# H01R0_Frontend_1.net
KiCad netlist of a schematic drawn in Altium Designer
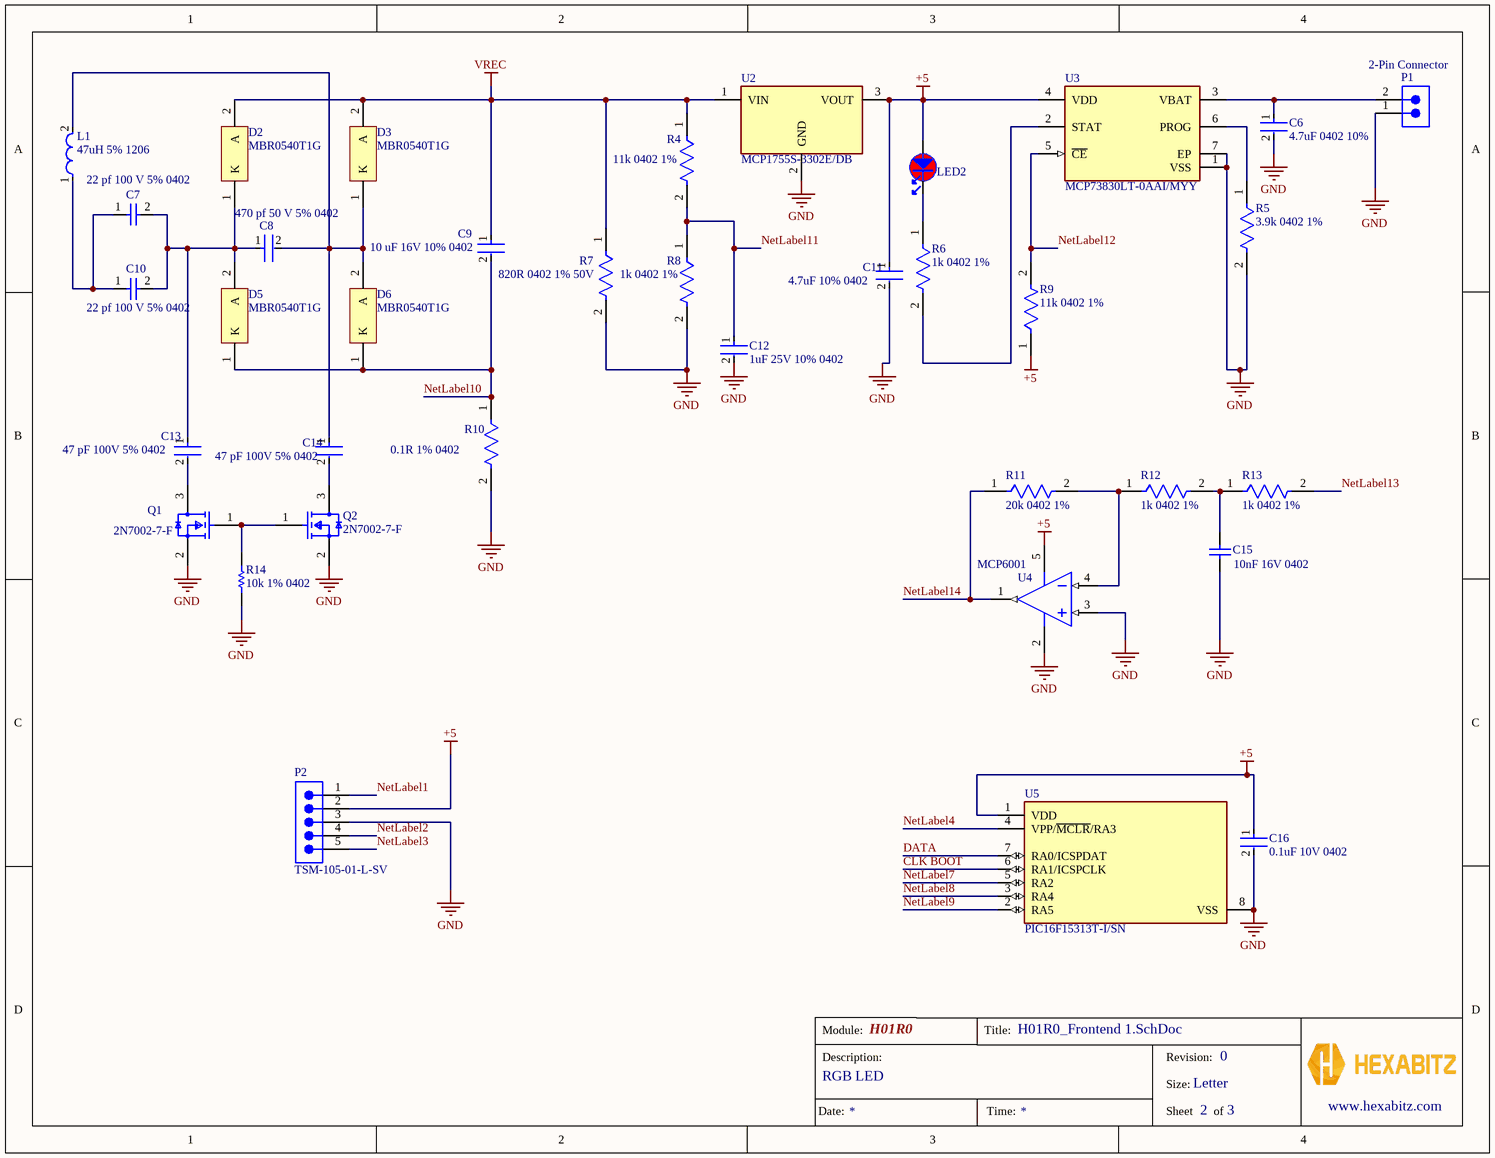
[diagram p0: H01R0_Frontend 1.SchDoc]

(export (version "E")
  (design (tool "Eeschema 10.0.6"))
  (components
    (comp (ref "C6")
      (value "4.7uF 0402 10%")
      (footprint "FP-GRM188-0_2-IPC_A")
      (description "Chip Multilayer Ceramic Capacitors for General Purpose, 0603, 4.7uF, X7S, 22%, 10%, 16V")
      (fields (field (name "TOLERANCE") "10%"))
      (libsource (lib "Altium Content Vault") (part "11868f565c42a9108669ba33697ecf6"))
    )
    (comp (ref "C7")
      (value "22 pf 100 V 5% 0402")
      (footprint "CAPC1005X61X26LL10T16")
      (fields (field (name "MANUFACTURER") "Vitramon") (field (name "PART NUMBER") "VJ0402D220JXBAJ"))
      (libsource (lib "") (part "CAP_1"))
    )
    (comp (ref "C8")
      (value "470 pf 50 V 5% 0402")
      (footprint "FP-C0402-BB-MFG")
      (description "C0402 470 pF C0G 0.05 50 V")
      (fields
        (field (name "MANUFACTURER PART NUMBER") "C0402C471J5GAC")
        (field (name "MANUFACTURER") "Kemet")
      )
      (libsource (lib "Altium Content Vault") (part "b4654b650e69147ec39a6b967a45e02"))
    )
    (comp (ref "C9")
      (value "10 uF 16V 10% 0402")
      (footprint "FP-GRM21B-0_1-IPC_B")
      (description "Chip Multilayer Ceramic Capacitors for General Purpose, 0805, 10uF, X6S, 22%, 10%, 16V")
      (fields (field (name "VOLTAGE") "16V") (field (name "TOLERANCE") "10%"))
      (libsource (lib "Altium Content Vault") (part "b4654b650e69147ec39a6b967a45e02"))
    )
    (comp (ref "C10")
      (value "22 pf 100 V 5% 0402")
      (footprint "CAPC1005X61X26LL10T16")
      (fields (field (name "MANUFACTURER") "Vitramon") (field (name "PART NUMBER") "VJ0402D220JXBAJ"))
      (libsource (lib "") (part "CAP_1"))
    )
    (comp (ref "C11")
      (value "4.7uF 10% 0402")
      (footprint "FP-GRM188-0_2-IPC_A")
      (description "Chip Multilayer Ceramic Capacitors for General Purpose, 0603, 4.7uF, X7S, 22%, 10%, 16V")
      (fields (field (name "TOLERANCE") "10%"))
      (libsource (lib "Altium Content Vault") (part "11868f565c42a9108669ba33697ecf6"))
    )
    (comp (ref "C12")
      (value "1uF 25V 10% 0402")
      (footprint "FP-GRM155-0_05-IPC_C")
      (description "Chip Multilayer Ceramic Capacitors for General Purpose, 0402, 1.0uF, B, 10%, 10%, 25V")
      (fields (field (name "TOLERANCE") "10%"))
      (libsource (lib "Altium Content Vault") (part "02cd4be3c70576c341d710602a673aa"))
    )
    (comp (ref "C13")
      (value "47 pF 100V 5% 0402")
      (footprint "FP-GQM155-0_05-IPC_A")
      (description "Ceramic Capacitor 47pF  ±5% 100VDC C0G 0402 Paper T/R")
      (fields (field (name "TOLERANCE") "5%"))
      (libsource (lib "Altium Content Vault") (part "11868f565c42a9108669ba33697ecf6"))
    )
    (comp (ref "C14")
      (value "47 pF 100V 5% 0402")
      (footprint "FP-GQM155-0_05-IPC_A")
      (description "Ceramic Capacitor 47pF  ±5% 100VDC C0G 0402 Paper T/R")
      (fields (field (name "TOLERANCE") "5%"))
      (libsource (lib "Altium Content Vault") (part "11868f565c42a9108669ba33697ecf6"))
    )
    (comp (ref "C15")
      (value "10nF 16V 0402")
      (footprint "CAPC1005X60X26LL10T16")
      (fields (field (name "MANUFACTURER") "Vitramon") (field (name "PART NUMBER") "VJ0402Y103KXJAC"))
      (libsource (lib "Altium Content Vault") (part "CAP"))
    )
    (comp (ref "C16")
      (value "0.1uF 10V 0402")
      (footprint "FP-C0402-BB-MFG")
      (description "CAP CER 0.1UF 10V X7R 0402")
      (fields (field (name "MANUFACTURER") "Kemet") (field (name "TOLERANCE") "0.1"))
      (libsource (lib "Altium Content Vault") (part "b4654b650e69147ec39a6b967a45e02"))
    )
    (comp (ref "D2")
      (value "MBR0540T1G")
      (footprint "ONSC-SOD-123-2-425-04_V")
      (description "Schottky Power Rectifier, 2-Pin SOD-123, Pb-Free, Tape and Reel")
      (fields (field (name "MANUFACTURER") "On Semiconductor"))
      (libsource (lib "Altium Content Vault") (part "ONSC-D-K1A2-2_A"))
    )
    (comp (ref "D3")
      (value "MBR0540T1G")
      (footprint "ONSC-SOD-123-2-425-04_V")
      (description "Schottky Power Rectifier, 2-Pin SOD-123, Pb-Free, Tape and Reel")
      (fields (field (name "MANUFACTURER") "On Semiconductor"))
      (libsource (lib "Altium Content Vault") (part "ONSC-D-K1A2-2_A"))
    )
    (comp (ref "D5")
      (value "MBR0540T1G")
      (footprint "ONSC-SOD-123-2-425-04_V")
      (description "Schottky Power Rectifier, 2-Pin SOD-123, Pb-Free, Tape and Reel")
      (fields (field (name "MANUFACTURER") "On Semiconductor"))
      (libsource (lib "Altium Content Vault") (part "ONSC-D-K1A2-2_A"))
    )
    (comp (ref "D6")
      (value "MBR0540T1G")
      (footprint "ONSC-SOD-123-2-425-04_V")
      (description "Schottky Power Rectifier, 2-Pin SOD-123, Pb-Free, Tape and Reel")
      (fields (field (name "MANUFACTURER") "On Semiconductor"))
      (libsource (lib "Altium Content Vault") (part "ONSC-D-K1A2-2_A"))
    )
    (comp (ref "L1")
      (value "47uH 5% 1206")
      (footprint "FP-LQH31CN_03-MFG")
      (description "Wire Wound Ferrite Inductor for General Circuits 47μH ±5% 10.4Ω 55mA 1206")
      (fields (field (name "TOLERANCE") "5%"))
      (libsource (lib "Altium Content Vault") (part "725321dda6339637d4d059423bc1c3c"))
    )
    (comp (ref "LED2")
      (value "VLMS1300-GS08")
      (footprint "FP-6_541-5092_01-4-MFG")
      (description "LED Uni-Color Super Red 639nm 2-Pin Chip 0603(1608Metric) T/R")
      (fields (field (name "MANUFACTURER") "Vishay Semiconductors"))
      (libsource (lib "Hexabitz Altium Library") (part "VLMS1300-GS08"))
    )
    (comp (ref "P1")
      (value "2-Pin Connector")
      (footprint "679302124022")
      (libsource (lib "Altium Content Vault") (part "Header_Male_1R_02P"))
    )
    (comp (ref "P2")
      (value "TSM-105-01-L-SV")
      (footprint "SMTC-TSM-105-01-X-SV")
      (description "0.025\" SQ Post Header, Surface Mount, Vertical, -55 to 125 degC, 2.54 mm Pitch, 5-Pin, Male, RoHS")
      (fields (field (name "MANUFACTURER") "Samtec"))
      (libsource (lib "Altium Content Vault") (part "SMTC-TSM-105-01-X-SV"))
    )
    (comp (ref "Q1")
      (value "2N7002-7-F")
      (footprint "FP-SOT23-MFG")
      (description "MOSFET N-CH 60V 115MA SOT23-3")
      (fields (field (name "VOLTAGE") "60V"))
      (libsource (lib "Altium Content Vault") (part "3b9c635fedb024a5347a57b145af9cc"))
    )
    (comp (ref "Q2")
      (value "2N7002-7-F")
      (footprint "FP-SOT23-MFG")
      (description "MOSFET N-CH 60V 115MA SOT23-3")
      (fields (field (name "VOLTAGE") "60V"))
      (libsource (lib "Altium Content Vault") (part "3b9c635fedb024a5347a57b145af9cc"))
    )
    (comp (ref "R4")
      (value "11k 0402 1%")
      (footprint "FP-CRCW0402-e3-IPC_B")
      (description "RES Thick Film, 11kΩ, 1%, 0.063W, 100ppm/°C, 0402")
      (fields (field (name "TOLERANCE") "1%"))
      (libsource (lib "Altium Content Vault") (part "1029c3af85768c4190bb7ad29bc67b5"))
    )
    (comp (ref "R5")
      (value "3.9k 0402 1%")
      (footprint "FP-RN73R1E-IPC_C")
      (description "3.9kΩ ±1% 0.063W, 1/16W Chip Resistor 0402 (1005 Metric) Moisture Resistant Thin Film")
      (libsource (lib "Altium Content Vault") (part "1029c3af85768c4190bb7ad29bc67b5"))
    )
    (comp (ref "R6")
      (value "1k 0402 1%")
      (footprint "FP-AC0402-IPC_C")
      (description "RES 1kΩ ±1% 0.063W 0402")
      (libsource (lib "Altium Content Vault") (part "1029c3af85768c4190bb7ad29bc67b5"))
    )
    (comp (ref "R7")
      (value "820R 0402 1% 50V")
      (footprint "FP-MCS0402-IPC_C")
      (description "RES SMD 1.2K OHM 1% 1/10W 0402")
      (fields (field (name "TOLERANCE") "1%"))
      (libsource (lib "Altium Content Vault") (part "1029c3af85768c4190bb7ad29bc67b5"))
    )
    (comp (ref "R8")
      (value "1k 0402 1%")
      (footprint "FP-RNCP0402-IPC_C")
      (description "1kΩ ±1% 0.1W 0402 High Power Anti-Sulfur Thin Film Chip Resistor")
      (fields (field (name "TOLERANCE") "1%"))
      (libsource (lib "Altium Content Vault") (part "1029c3af85768c4190bb7ad29bc67b5"))
    )
    (comp (ref "R9")
      (value "11k 0402 1%")
      (footprint "FP-CRCW0402-e3-IPC_B")
      (description "RES Thick Film, 11kΩ, 1%, 0.063W, 100ppm/°C, 0402")
      (fields (field (name "TOLERANCE") "1%"))
      (libsource (lib "Altium Content Vault") (part "1029c3af85768c4190bb7ad29bc67b5"))
    )
    (comp (ref "R10")
      (value "0.1R 1% 0402")
      (footprint "FP-CSR0402-IPC_A")
      (description "General Purpose Thick Film Chip Resistor, 0402, 0.1Ω, 1%, 200ppm/°C, 0.125W")
      (fields (field (name "TOLERANCE") "1%"))
      (libsource (lib "Altium Content Vault") (part "1029c3af85768c4190bb7ad29bc67b5"))
    )
    (comp (ref "R11")
      (value "20k 0402 1%")
      (footprint "FP-TFCR0402-IPC_A")
      (description "RES Thin Film,  20kΩ, 1%, 0.063W, 50ppm/°C, 0402")
      (libsource (lib "Altium Content Vault") (part "1029c3af85768c4190bb7ad29bc67b5"))
    )
    (comp (ref "R12")
      (value "1k 0402 1%")
      (footprint "FP-RNCP0402-IPC_C")
      (description "1kΩ ±1% 0.1W 0402 High Power Anti-Sulfur Thin Film Chip Resistor")
      (fields (field (name "TOLERANCE") "1%"))
      (libsource (lib "Altium Content Vault") (part "1029c3af85768c4190bb7ad29bc67b5"))
    )
    (comp (ref "R13")
      (value "1k 0402 1%")
      (footprint "FP-RNCP0402-IPC_C")
      (description "1kΩ ±1% 0.1W 0402 High Power Anti-Sulfur Thin Film Chip Resistor")
      (fields (field (name "TOLERANCE") "1%"))
      (libsource (lib "Altium Content Vault") (part "1029c3af85768c4190bb7ad29bc67b5"))
    )
    (comp (ref "R14")
      (value "10k 1% 0402")
      (footprint "RESC1005X40X25LL10T10")
      (fields (field (name "MANUFACTURER") "KOA Speer") (field (name "PART NUMBER") "SG73P1ETTP1002F"))
      (libsource (lib "Altium Content Vault") (part "RES"))
    )
    (comp (ref "U2")
      (value "MCP1755S-3302E/DB")
      (footprint "FP-C04-032-MFG")
      (description "IC REG LIN 3.3V 300MA SOT223-3")
      (fields (field (name "TOLERANCE") "2%"))
      (libsource (lib "Altium Content Vault") (part "0edcb772792940466765807cac25de9"))
    )
    (comp (ref "U3")
      (value "MCP73830LT-0AAI/MYY")
      (footprint "FP-C04-078-IPC_C")
      (description "IC BATT CHG LI-ION 1CELL 6TDFN")
      (libsource (lib "Altium Content Vault") (part "eab4c6cdc0eba9ee105b8b64542a710"))
    )
    (comp (ref "U4")
      (value "MCP6001")
      (footprint "SOT-23-OT5_L")
      (description "None")
      (fields (field (name "VOLTAGE") "6V"))
      (libsource (lib "Altium Content Vault") (part "AMP-OPA-MCP6001-SOT5"))
    )
    (comp (ref "U5")
      (value "PIC16F15313T-I/SN")
      (footprint "FP-C04-057-MFG")
      (description "IC MCU 8BIT 3.5KB FLASH 8SOIC")
      (libsource (lib "Altium Content Vault") (part "1bfb033732aabc110c1c0aa1af68e8c"))
    )
  )
  (nets
    (net (code "1") (name "+5") (class "Default")
      (node (ref "C11") (pin "1") (pinfunction "1_1") (pintype "passive"))
      (node (ref "C16") (pin "1") (pinfunction "1_1") (pintype "passive"))
      (node (ref "LED2") (pin "2") (pintype "passive"))
      (node (ref "P2") (pin "2") (pinfunction "2_2") (pintype "passive"))
      (node (ref "R9") (pin "1") (pinfunction "1_1") (pintype "passive"))
      (node (ref "U2") (pin "3") (pinfunction "VOUT_3") (pintype "passive"))
      (node (ref "U3") (pin "4") (pinfunction "VDD_4") (pintype "power_in"))
      (node (ref "U4") (pin "5") (pinfunction "VDD_5") (pintype "power_in"))
      (node (ref "U5") (pin "1") (pinfunction "VDD_1") (pintype "power_in"))
    )
    (net (code "2") (name "/CLK BOOT") (class "Default")
      (node (ref "U5") (pin "6") (pinfunction "RA1/ICSPCLK_6") (pintype "bidirectional"))
    )
    (net (code "3") (name "/DATA") (class "Default")
      (node (ref "U5") (pin "7") (pinfunction "RA0/ICSPDAT_7") (pintype "bidirectional"))
    )
    (net (code "4") (name "/NetLabel1") (class "Default")
      (node (ref "P2") (pin "1") (pinfunction "1_1") (pintype "passive"))
    )
    (net (code "5") (name "/NetLabel2") (class "Default")
      (node (ref "P2") (pin "4") (pinfunction "4_4") (pintype "passive"))
    )
    (net (code "6") (name "/NetLabel3") (class "Default")
      (node (ref "P2") (pin "5") (pinfunction "5_5") (pintype "passive"))
    )
    (net (code "7") (name "/NetLabel4") (class "Default")
      (node (ref "U5") (pin "4") (pinfunction "VPP/~{MCLR}/RA3_4") (pintype "power_in"))
    )
    (net (code "8") (name "/NetLabel7") (class "Default")
      (node (ref "U5") (pin "5") (pinfunction "RA2_5") (pintype "bidirectional"))
    )
    (net (code "9") (name "/NetLabel8") (class "Default")
      (node (ref "U5") (pin "3") (pinfunction "RA4_3") (pintype "bidirectional"))
    )
    (net (code "10") (name "/NetLabel9") (class "Default")
      (node (ref "U5") (pin "2") (pinfunction "RA5_2") (pintype "bidirectional"))
    )
    (net (code "11") (name "/NetLabel10") (class "Default")
      (node (ref "C9") (pin "2") (pinfunction "2_2") (pintype "passive"))
      (node (ref "D5") (pin "1") (pinfunction "K_1") (pintype "passive"))
      (node (ref "D6") (pin "1") (pinfunction "K_1") (pintype "passive"))
      (node (ref "R10") (pin "1") (pinfunction "1_1") (pintype "passive"))
    )
    (net (code "12") (name "/NetLabel11") (class "Default")
      (node (ref "C12") (pin "1") (pinfunction "1_1") (pintype "passive"))
      (node (ref "R4") (pin "2") (pinfunction "2_2") (pintype "passive"))
      (node (ref "R8") (pin "1") (pinfunction "1_1") (pintype "passive"))
    )
    (net (code "13") (name "/NetLabel12") (class "Default")
      (node (ref "R9") (pin "2") (pinfunction "2_2") (pintype "passive"))
      (node (ref "U3") (pin "5") (pinfunction "~{CE}_5") (pintype "input"))
    )
    (net (code "14") (name "/NetLabel13") (class "Default")
      (node (ref "R13") (pin "2") (pinfunction "2_2") (pintype "passive"))
    )
    (net (code "15") (name "/NetLabel14") (class "Default")
      (node (ref "R11") (pin "1") (pinfunction "1_1") (pintype "passive"))
      (node (ref "U4") (pin "1") (pinfunction "VOUT_1") (pintype "output"))
    )
    (net (code "16") (name "GND") (class "Default")
      (node (ref "C11") (pin "2") (pinfunction "2_2") (pintype "passive"))
      (node (ref "C12") (pin "2") (pinfunction "2_2") (pintype "passive"))
      (node (ref "C15") (pin "2") (pinfunction "2_2") (pintype "passive"))
      (node (ref "C16") (pin "2") (pinfunction "2_2") (pintype "passive"))
      (node (ref "C6") (pin "2") (pinfunction "2_2") (pintype "passive"))
      (node (ref "P1") (pin "1") (pinfunction "1_1") (pintype "passive"))
      (node (ref "P2") (pin "3") (pinfunction "3_3") (pintype "passive"))
      (node (ref "Q1") (pin "2") (pinfunction "S_2") (pintype "passive"))
      (node (ref "Q2") (pin "2") (pinfunction "S_2") (pintype "passive"))
      (node (ref "R10") (pin "2") (pinfunction "2_2") (pintype "passive"))
      (node (ref "R14") (pin "1") (pinfunction "1_1") (pintype "passive"))
      (node (ref "R5") (pin "2") (pinfunction "2_2") (pintype "passive"))
      (node (ref "R7") (pin "2") (pinfunction "2_2") (pintype "passive"))
      (node (ref "R8") (pin "2") (pinfunction "2_2") (pintype "passive"))
      (node (ref "U2") (pin "2") (pinfunction "GND_2") (pintype "power_in"))
      (node (ref "U3") (pin "1") (pinfunction "VSS_1") (pintype "power_in"))
      (node (ref "U3") (pin "7") (pinfunction "EP_7") (pintype "power_in"))
      (node (ref "U4") (pin "2") (pinfunction "VSS_2") (pintype "power_in"))
      (node (ref "U4") (pin "3") (pinfunction "VIN+_3") (pintype "input"))
      (node (ref "U5") (pin "8") (pinfunction "VSS_8") (pintype "power_in"))
    )
    (net (code "17") (name "Net-(C10-Pad1)") (class "Default")
      (node (ref "C10") (pin "1") (pinfunction "1_1") (pintype "passive"))
      (node (ref "C7") (pin "1") (pinfunction "1_1") (pintype "passive"))
      (node (ref "L1") (pin "1") (pinfunction "1_1") (pintype "passive"))
    )
    (net (code "18") (name "Net-(C15-Pad1)") (class "Default")
      (node (ref "C15") (pin "1") (pinfunction "1_1") (pintype "passive"))
      (node (ref "R12") (pin "2") (pinfunction "2_2") (pintype "passive"))
      (node (ref "R13") (pin "1") (pinfunction "1_1") (pintype "passive"))
    )
    (net (code "19") (name "Net-(D2-K)") (class "Default")
      (node (ref "C10") (pin "2") (pinfunction "2_2") (pintype "passive"))
      (node (ref "C13") (pin "1") (pinfunction "1_1") (pintype "passive"))
      (node (ref "C7") (pin "2") (pinfunction "2_2") (pintype "passive"))
      (node (ref "C8") (pin "1") (pinfunction "1_1") (pintype "passive"))
      (node (ref "D2") (pin "1") (pinfunction "K_1") (pintype "passive"))
      (node (ref "D5") (pin "2") (pinfunction "A_2") (pintype "passive"))
    )
    (net (code "20") (name "Net-(D3-K)") (class "Default")
      (node (ref "C14") (pin "1") (pinfunction "1_1") (pintype "passive"))
      (node (ref "C8") (pin "2") (pinfunction "2_2") (pintype "passive"))
      (node (ref "D3") (pin "1") (pinfunction "K_1") (pintype "passive"))
      (node (ref "D6") (pin "2") (pinfunction "A_2") (pintype "passive"))
      (node (ref "L1") (pin "2") (pinfunction "2_2") (pintype "passive"))
    )
    (net (code "21") (name "Net-(LED2-Pad1)") (class "Default")
      (node (ref "LED2") (pin "1") (pintype "passive"))
      (node (ref "R6") (pin "1") (pinfunction "1_1") (pintype "passive"))
    )
    (net (code "22") (name "Net-(Q1-D)") (class "Default")
      (node (ref "C13") (pin "2") (pinfunction "2_2") (pintype "passive"))
      (node (ref "Q1") (pin "3") (pinfunction "D_3") (pintype "passive"))
    )
    (net (code "23") (name "Net-(Q1-G)") (class "Default")
      (node (ref "Q1") (pin "1") (pinfunction "G_1") (pintype "passive"))
      (node (ref "Q2") (pin "1") (pinfunction "G_1") (pintype "passive"))
      (node (ref "R14") (pin "2") (pinfunction "2_2") (pintype "passive"))
    )
    (net (code "24") (name "Net-(Q2-D)") (class "Default")
      (node (ref "C14") (pin "2") (pinfunction "2_2") (pintype "passive"))
      (node (ref "Q2") (pin "3") (pinfunction "D_3") (pintype "passive"))
    )
    (net (code "25") (name "Net-(U3-PROG)") (class "Default")
      (node (ref "R5") (pin "1") (pinfunction "1_1") (pintype "passive"))
      (node (ref "U3") (pin "6") (pinfunction "PROG_6") (pintype "passive"))
    )
    (net (code "26") (name "Net-(U3-STAT)") (class "Default")
      (node (ref "R6") (pin "2") (pinfunction "2_2") (pintype "passive"))
      (node (ref "U3") (pin "2") (pinfunction "STAT_2") (pintype "passive"))
    )
    (net (code "27") (name "Net-(U3-VBAT)") (class "Default")
      (node (ref "C6") (pin "1") (pinfunction "1_1") (pintype "passive"))
      (node (ref "P1") (pin "2") (pinfunction "2_2") (pintype "passive"))
      (node (ref "U3") (pin "3") (pinfunction "VBAT_3") (pintype "power_in"))
    )
    (net (code "28") (name "Net-(U4-VIN-)") (class "Default")
      (node (ref "R11") (pin "2") (pinfunction "2_2") (pintype "passive"))
      (node (ref "R12") (pin "1") (pinfunction "1_1") (pintype "passive"))
      (node (ref "U4") (pin "4") (pinfunction "VIN-_4") (pintype "input"))
    )
    (net (code "29") (name "VREC") (class "Default")
      (node (ref "C9") (pin "1") (pinfunction "1_1") (pintype "passive"))
      (node (ref "D2") (pin "2") (pinfunction "A_2") (pintype "passive"))
      (node (ref "D3") (pin "2") (pinfunction "A_2") (pintype "passive"))
      (node (ref "R4") (pin "1") (pinfunction "1_1") (pintype "passive"))
      (node (ref "R7") (pin "1") (pinfunction "1_1") (pintype "passive"))
      (node (ref "U2") (pin "1") (pinfunction "VIN_1") (pintype "power_in"))
    )
  )
)
